# Adafruit_Gemma_M0.net
KiCad netlist of a schematic drawn in EAGLE
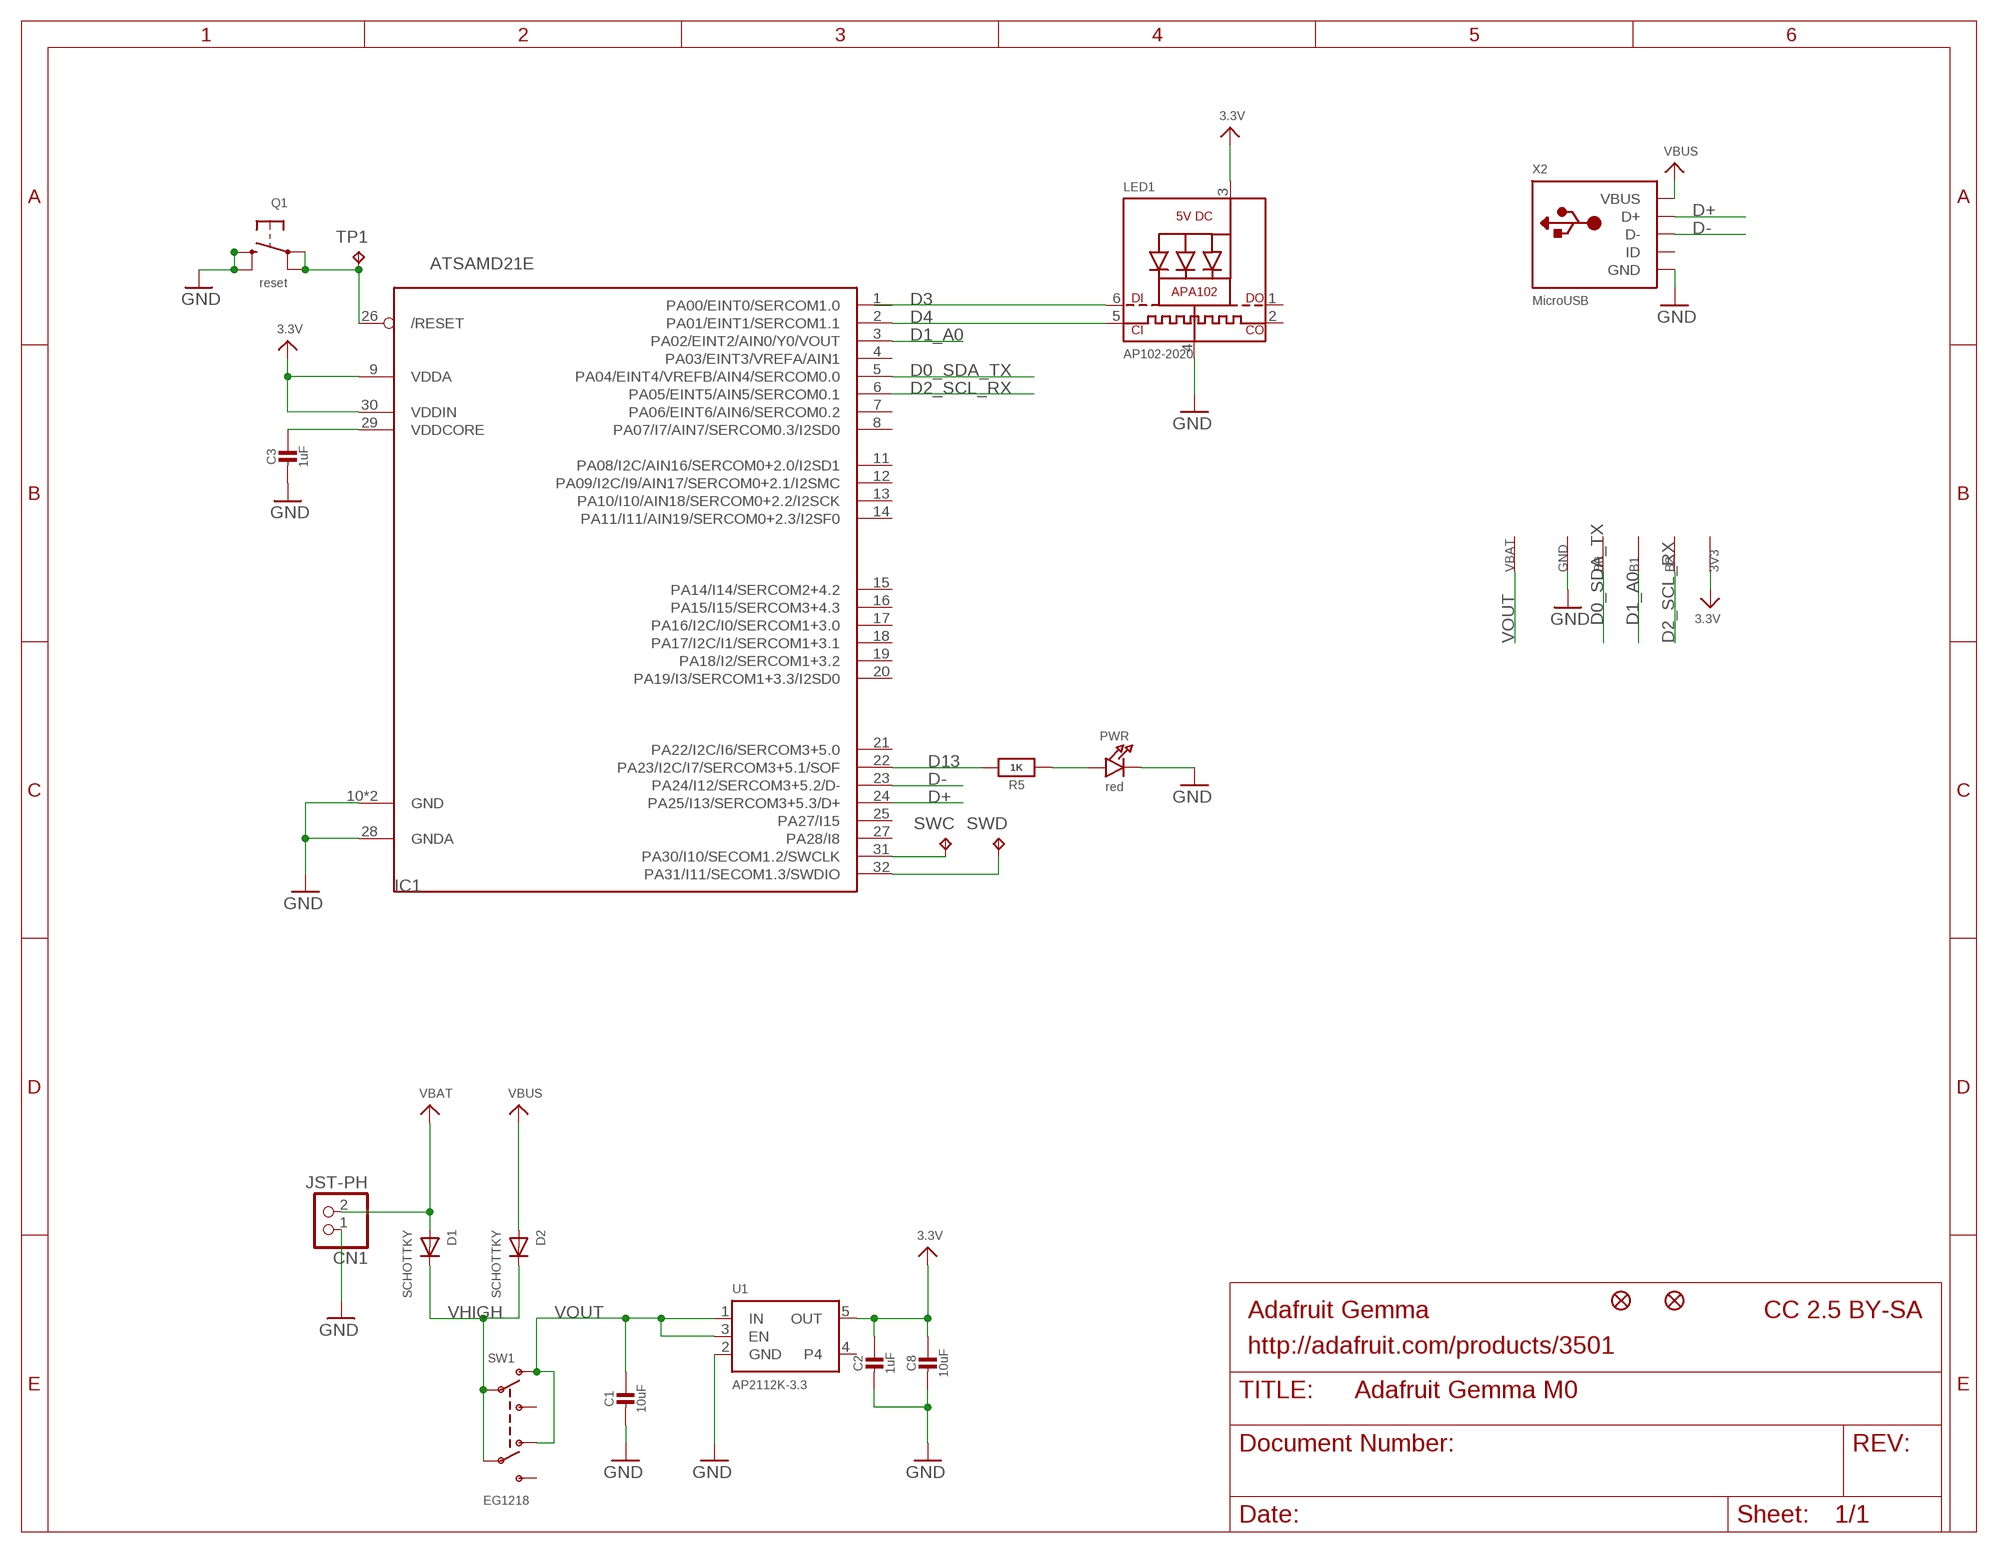
[diagram p0: schematic, sheet 1]

(export (version "E")
  (design (tool "Eeschema 10.0.6"))
  (components
    (comp (ref "3V3")
      (value "SEWTAP-ALLIGATOR")
      (footprint "eagle-import:SEWALLI")
      (libsource (lib "eagle-import") (part "SEWTAP-ALLIGATOR"))
    )
    (comp (ref "B0")
      (value "SEWTAP-ALLIGATOR")
      (footprint "eagle-import:SEWALLI")
      (libsource (lib "eagle-import") (part "SEWTAP-ALLIGATOR"))
    )
    (comp (ref "B1")
      (value "SEWTAP-ALLIGATOR")
      (footprint "eagle-import:SEWALLI")
      (libsource (lib "eagle-import") (part "SEWTAP-ALLIGATOR"))
    )
    (comp (ref "B2")
      (value "SEWTAP-ALLIGATOR")
      (footprint "eagle-import:SEWALLI")
      (libsource (lib "eagle-import") (part "SEWTAP-ALLIGATOR"))
    )
    (comp (ref "C1")
      (value "10uF")
      (footprint "eagle-import:0805-NO")
      (libsource (lib "eagle-import") (part "CAP_CERAMIC0805-NOOUTLINE"))
    )
    (comp (ref "C2")
      (value "1uF")
      (footprint "eagle-import:0603-NO")
      (libsource (lib "eagle-import") (part "CAP_CERAMIC0603_NO"))
    )
    (comp (ref "C3")
      (value "1uF")
      (footprint "eagle-import:0603-NO")
      (libsource (lib "eagle-import") (part "CAP_CERAMIC0603_NO"))
    )
    (comp (ref "C8")
      (value "10uF")
      (footprint "eagle-import:0805-NO")
      (libsource (lib "eagle-import") (part "CAP_CERAMIC0805-NOOUTLINE"))
    )
    (comp (ref "CN1")
      (value "JST-PH")
      (footprint "eagle-import:JSTPH2")
      (libsource (lib "eagle-import") (part "CON_JST_PH_2PIN"))
    )
    (comp (ref "D1")
      (value "SCHOTTKY")
      (footprint "eagle-import:SOD-123FL")
      (libsource (lib "eagle-import") (part "DIODE_SOD-123FL"))
    )
    (comp (ref "D2")
      (value "SCHOTTKY")
      (footprint "eagle-import:SOD-123FL")
      (libsource (lib "eagle-import") (part "DIODE_SOD-123FL"))
    )
    (comp (ref "GND")
      (value "SEWTAP-ALLIGATOR")
      (footprint "eagle-import:SEWALLI")
      (libsource (lib "eagle-import") (part "SEWTAP-ALLIGATOR"))
    )
    (comp (ref "IC1")
      (value "ATSAMD21E")
      (footprint "eagle-import:QFN32_5MM")
      (libsource (lib "eagle-import") (part "ATSAMD21E"))
    )
    (comp (ref "LED1")
      (value "AP102-2020")
      (footprint "eagle-import:APA102_2020")
      (libsource (lib "eagle-import") (part "APA1022020"))
    )
    (comp (ref "PWR")
      (value "red")
      (footprint "eagle-import:CHIPLED_0603_NOOUTLINE")
      (libsource (lib "eagle-import") (part "LED0603_NOOUTLINE"))
    )
    (comp (ref "Q1")
      (value "reset")
      (footprint "eagle-import:BTN_KMR2_4.6X2.8")
      (libsource (lib "eagle-import") (part "SWITCH_TACT_SMT4.6X2.8"))
    )
    (comp (ref "R5")
      (value "1K")
      (footprint "eagle-import:0603-NO")
      (libsource (lib "eagle-import") (part "RESISTOR_0603_NOOUT"))
    )
    (comp (ref "SW1")
      (value "EG1218")
      (footprint "eagle-import:EG1390")
      (libsource (lib "eagle-import") (part "SWITCH_DPDTEG1390"))
    )
    (comp (ref "SWC")
      (value "TPTP15R")
      (footprint "eagle-import:TP15R")
      (libsource (lib "eagle-import") (part "TPTP15R"))
    )
    (comp (ref "SWD")
      (value "TPTP15R")
      (footprint "eagle-import:TP15R")
      (libsource (lib "eagle-import") (part "TPTP15R"))
    )
    (comp (ref "TP1")
      (value "TPTP16R")
      (footprint "eagle-import:TP16R")
      (libsource (lib "eagle-import") (part "TPTP16R"))
    )
    (comp (ref "U$1")
      (value "FIDUCIAL_1MM")
      (footprint "eagle-import:FIDUCIAL_1MM")
      (libsource (lib "eagle-import") (part "FIDUCIAL_1MM"))
    )
    (comp (ref "U$6")
      (value "FIDUCIAL_1MM")
      (footprint "eagle-import:FIDUCIAL_1MM")
      (libsource (lib "eagle-import") (part "FIDUCIAL_1MM"))
    )
    (comp (ref "U1")
      (value "AP2112K-3.3")
      (footprint "eagle-import:SOT23-5")
      (libsource (lib "eagle-import") (part "VREG_SOT23-5"))
    )
    (comp (ref "VBAT")
      (value "SEWTAP-ALLIGATOR")
      (footprint "eagle-import:SEWALLI")
      (libsource (lib "eagle-import") (part "SEWTAP-ALLIGATOR"))
    )
    (comp (ref "X2")
      (value "MicroUSB")
      (footprint "eagle-import:4UCONN_20329_V2")
      (libsource (lib "eagle-import") (part "USB_MICRO_20329_V2"))
    )
  )
  (nets
    (net (code "1") (name "/D+") (class "Default")
      (node (ref "IC1") (pin "24") (pinfunction "PA25/I13/SERCOM3+5.3/D+_24") (pintype "bidirectional"))
      (node (ref "X2") (pin "D+") (pinfunction "D+_D+") (pintype "bidirectional"))
    )
    (net (code "2") (name "/D-") (class "Default")
      (node (ref "IC1") (pin "23") (pinfunction "PA24/I12/SERCOM3+5.2/D-_23") (pintype "bidirectional"))
      (node (ref "X2") (pin "D-") (pinfunction "D-_D-") (pintype "bidirectional"))
    )
    (net (code "3") (name "/D0_SDA_TX") (class "Default")
      (node (ref "B0") (pin "P$1") (pinfunction "SEW_P$1") (pintype "bidirectional"))
      (node (ref "IC1") (pin "5") (pinfunction "PA04/EINT4/VREFB/AIN4/SERCOM0.0_5") (pintype "bidirectional"))
    )
    (net (code "4") (name "/D1_A0") (class "Default")
      (node (ref "B1") (pin "P$1") (pinfunction "SEW_P$1") (pintype "bidirectional"))
      (node (ref "IC1") (pin "3") (pinfunction "PA02/EINT2/AIN0/Y0/VOUT_3") (pintype "bidirectional"))
    )
    (net (code "5") (name "/D2_SCL_RX") (class "Default")
      (node (ref "B2") (pin "P$1") (pinfunction "SEW_P$1") (pintype "bidirectional"))
      (node (ref "IC1") (pin "6") (pinfunction "PA05/EINT5/AIN5/SERCOM0.1_6") (pintype "bidirectional"))
    )
    (net (code "6") (name "/D3") (class "Default")
      (node (ref "IC1") (pin "1") (pinfunction "PA00/EINT0/SERCOM1.0_1") (pintype "bidirectional"))
      (node (ref "LED1") (pin "6") (pinfunction "DI_6") (pintype "input"))
    )
    (net (code "7") (name "/D4") (class "Default")
      (node (ref "IC1") (pin "2") (pinfunction "PA01/EINT1/SERCOM1.1_2") (pintype "bidirectional"))
      (node (ref "LED1") (pin "5") (pinfunction "CKI_5") (pintype "input"))
    )
    (net (code "8") (name "/D13") (class "Default")
      (node (ref "IC1") (pin "22") (pinfunction "PA23/I2C/I7/SERCOM3+5.1/SOF_22") (pintype "bidirectional"))
      (node (ref "R5") (pin "2") (pinfunction "2_2") (pintype "passive"))
    )
    (net (code "9") (name "/VHIGH") (class "Default")
      (node (ref "D1") (pin "C") (pinfunction "C_C") (pintype "passive"))
      (node (ref "D2") (pin "C") (pinfunction "C_C") (pintype "passive"))
      (node (ref "SW1") (pin "P1") (pinfunction "P1_P1") (pintype "passive"))
      (node (ref "SW1") (pin "P2") (pinfunction "P2_P2") (pintype "passive"))
    )
    (net (code "10") (name "/VOUT") (class "Default")
      (node (ref "C1") (pin "1") (pinfunction "1_1") (pintype "passive"))
      (node (ref "SW1") (pin "O1") (pinfunction "O1_O1") (pintype "passive"))
      (node (ref "SW1") (pin "O2") (pinfunction "O2_O2") (pintype "passive"))
      (node (ref "U1") (pin "1") (pinfunction "IN_1") (pintype "power_in"))
      (node (ref "U1") (pin "3") (pinfunction "EN_3") (pintype "input"))
      (node (ref "VBAT") (pin "P$1") (pinfunction "SEW_P$1") (pintype "bidirectional"))
    )
    (net (code "11") (name "3.3V") (class "Default")
      (node (ref "3V3") (pin "P$1") (pinfunction "SEW_P$1") (pintype "bidirectional"))
      (node (ref "C2") (pin "1") (pinfunction "1_1") (pintype "passive"))
      (node (ref "C8") (pin "1") (pinfunction "1_1") (pintype "passive"))
      (node (ref "IC1") (pin "30") (pinfunction "VDDIN_30") (pintype "power_in"))
      (node (ref "IC1") (pin "9") (pinfunction "VDDA_9") (pintype "power_in"))
      (node (ref "LED1") (pin "3") (pinfunction "VDD_3") (pintype "power_in"))
      (node (ref "U1") (pin "5") (pinfunction "OUT_5") (pintype "power_in"))
    )
    (net (code "12") (name "GND") (class "Default")
      (node (ref "C1") (pin "2") (pinfunction "2_2") (pintype "passive"))
      (node (ref "C2") (pin "2") (pinfunction "2_2") (pintype "passive"))
      (node (ref "C3") (pin "2") (pinfunction "2_2") (pintype "passive"))
      (node (ref "C8") (pin "2") (pinfunction "2_2") (pintype "passive"))
      (node (ref "CN1") (pin "1") (pinfunction "1_1") (pintype "passive"))
      (node (ref "GND") (pin "P$1") (pinfunction "SEW_P$1") (pintype "bidirectional"))
      (node (ref "IC1") (pin "10") (pinfunction "GND_10") (pintype "power_in"))
      (node (ref "IC1") (pin "28") (pinfunction "GNDA_28") (pintype "power_in"))
      (node (ref "IC1") (pin "33") (pinfunction "GND_33") (pintype "power_in"))
      (node (ref "LED1") (pin "4") (pinfunction "GND_4") (pintype "power_in"))
      (node (ref "PWR") (pin "C") (pinfunction "C_C") (pintype "passive"))
      (node (ref "Q1") (pin "B") (pinfunction "S_B") (pintype "passive"))
      (node (ref "Q1") (pin "B'") (pinfunction "S1_B'") (pintype "passive"))
      (node (ref "U1") (pin "2") (pinfunction "GND_2") (pintype "power_in"))
      (node (ref "X2") (pin "BASE@1") (pinfunction "GND_BASE@1") (pintype "power_in"))
      (node (ref "X2") (pin "BASE@2") (pinfunction "GND_BASE@2") (pintype "power_in"))
      (node (ref "X2") (pin "GND") (pinfunction "GND_GND") (pintype "power_in"))
      (node (ref "X2") (pin "SPRT@1") (pinfunction "GND_SPRT@1") (pintype "power_in"))
      (node (ref "X2") (pin "SPRT@2") (pinfunction "GND_SPRT@2") (pintype "power_in"))
      (node (ref "X2") (pin "SPRT@3") (pinfunction "GND_SPRT@3") (pintype "power_in"))
      (node (ref "X2") (pin "SPRT@4") (pinfunction "GND_SPRT@4") (pintype "power_in"))
    )
    (net (code "13") (name "Net-(IC1-PA30{slash}I10{slash}SECOM1.2{slash}SWCLK)") (class "Default")
      (node (ref "IC1") (pin "31") (pinfunction "PA30/I10/SECOM1.2/SWCLK_31") (pintype "bidirectional"))
      (node (ref "SWC") (pin "TP") (pinfunction "TP_TP") (pintype "input"))
    )
    (net (code "14") (name "Net-(IC1-PA31{slash}I11{slash}SECOM1.3{slash}SWDIO)") (class "Default")
      (node (ref "IC1") (pin "32") (pinfunction "PA31/I11/SECOM1.3/SWDIO_32") (pintype "bidirectional"))
      (node (ref "SWD") (pin "TP") (pinfunction "TP_TP") (pintype "input"))
    )
    (net (code "15") (name "Net-(IC1-VDDCORE)") (class "Default")
      (node (ref "C3") (pin "1") (pinfunction "1_1") (pintype "passive"))
      (node (ref "IC1") (pin "29") (pinfunction "VDDCORE_29") (pintype "power_in"))
    )
    (net (code "16") (name "Net-(IC1-{slash}RESET)") (class "Default")
      (node (ref "IC1") (pin "26") (pinfunction "/RESET_26") (pintype "bidirectional"))
      (node (ref "Q1") (pin "A") (pinfunction "P_A") (pintype "passive"))
      (node (ref "Q1") (pin "A'") (pinfunction "P1_A'") (pintype "passive"))
      (node (ref "TP1") (pin "TP") (pinfunction "TP_TP") (pintype "input"))
    )
    (net (code "17") (name "Net-(PWR-PadA)") (class "Default")
      (node (ref "PWR") (pin "A") (pinfunction "A_A") (pintype "passive"))
      (node (ref "R5") (pin "1") (pinfunction "1_1") (pintype "passive"))
    )
    (net (code "18") (name "VBAT") (class "Default")
      (node (ref "CN1") (pin "2") (pinfunction "2_2") (pintype "passive"))
      (node (ref "D1") (pin "A") (pinfunction "A_A") (pintype "passive"))
    )
    (net (code "19") (name "VBUS") (class "Default")
      (node (ref "D2") (pin "A") (pinfunction "A_A") (pintype "passive"))
      (node (ref "X2") (pin "VBUS") (pinfunction "VBUS_VBUS") (pintype "power_in"))
    )
    (net (code "20") (name "unconnected-(IC1-PA03{slash}EINT3{slash}VREFA{slash}AIN1-Pad4)") (class "Default")
      (node (ref "IC1") (pin "4") (pinfunction "PA03/EINT3/VREFA/AIN1_4") (pintype "bidirectional"))
    )
    (net (code "21") (name "unconnected-(IC1-PA06{slash}EINT6{slash}AIN6{slash}SERCOM0.2-Pad7)") (class "Default")
      (node (ref "IC1") (pin "7") (pinfunction "PA06/EINT6/AIN6/SERCOM0.2_7") (pintype "bidirectional"))
    )
    (net (code "22") (name "unconnected-(IC1-PA07{slash}I7{slash}AIN7{slash}SERCOM0.3{slash}I2SD0-Pad8)") (class "Default")
      (node (ref "IC1") (pin "8") (pinfunction "PA07/I7/AIN7/SERCOM0.3/I2SD0_8") (pintype "bidirectional"))
    )
    (net (code "23") (name "unconnected-(IC1-PA08{slash}I2C{slash}AIN16{slash}SERCOM0+2.0{slash}I2SD1-Pad11)") (class "Default")
      (node (ref "IC1") (pin "11") (pinfunction "PA08/I2C/AIN16/SERCOM0+2.0/I2SD1_11") (pintype "bidirectional"))
    )
    (net (code "24") (name "unconnected-(IC1-PA09{slash}I2C{slash}I9{slash}AIN17{slash}SERCOM0+2.1{slash}I2SMC-Pad12)") (class "Default")
      (node (ref "IC1") (pin "12") (pinfunction "PA09/I2C/I9/AIN17/SERCOM0+2.1/I2SMC_12") (pintype "bidirectional"))
    )
    (net (code "25") (name "unconnected-(IC1-PA10{slash}I10{slash}AIN18{slash}SERCOM0+2.2{slash}I2SCK-Pad13)") (class "Default")
      (node (ref "IC1") (pin "13") (pinfunction "PA10/I10/AIN18/SERCOM0+2.2/I2SCK_13") (pintype "bidirectional"))
    )
    (net (code "26") (name "unconnected-(IC1-PA11{slash}I11{slash}AIN19{slash}SERCOM0+2.3{slash}I2SF0-Pad14)") (class "Default")
      (node (ref "IC1") (pin "14") (pinfunction "PA11/I11/AIN19/SERCOM0+2.3/I2SF0_14") (pintype "bidirectional"))
    )
    (net (code "27") (name "unconnected-(IC1-PA14{slash}I14{slash}SERCOM2+4.2-Pad15)") (class "Default")
      (node (ref "IC1") (pin "15") (pinfunction "PA14/I14/SERCOM2+4.2_15") (pintype "bidirectional"))
    )
    (net (code "28") (name "unconnected-(IC1-PA15{slash}I15{slash}SERCOM3+4.3-Pad16)") (class "Default")
      (node (ref "IC1") (pin "16") (pinfunction "PA15/I15/SERCOM3+4.3_16") (pintype "bidirectional"))
    )
    (net (code "29") (name "unconnected-(IC1-PA16{slash}I2C{slash}I0{slash}SERCOM1+3.0-Pad17)") (class "Default")
      (node (ref "IC1") (pin "17") (pinfunction "PA16/I2C/I0/SERCOM1+3.0_17") (pintype "bidirectional"))
    )
    (net (code "30") (name "unconnected-(IC1-PA17{slash}I2C{slash}I1{slash}SERCOM1+3.1-Pad18)") (class "Default")
      (node (ref "IC1") (pin "18") (pinfunction "PA17/I2C/I1/SERCOM1+3.1_18") (pintype "bidirectional"))
    )
    (net (code "31") (name "unconnected-(IC1-PA18{slash}I2{slash}SERCOM1+3.2-Pad19)") (class "Default")
      (node (ref "IC1") (pin "19") (pinfunction "PA18/I2/SERCOM1+3.2_19") (pintype "bidirectional"))
    )
    (net (code "32") (name "unconnected-(IC1-PA19{slash}I3{slash}SERCOM1+3.3{slash}I2SD0-Pad20)") (class "Default")
      (node (ref "IC1") (pin "20") (pinfunction "PA19/I3/SERCOM1+3.3/I2SD0_20") (pintype "bidirectional"))
    )
    (net (code "33") (name "unconnected-(IC1-PA22{slash}I2C{slash}I6{slash}SERCOM3+5.0-Pad21)") (class "Default")
      (node (ref "IC1") (pin "21") (pinfunction "PA22/I2C/I6/SERCOM3+5.0_21") (pintype "bidirectional"))
    )
    (net (code "34") (name "unconnected-(IC1-PA27{slash}I15-Pad25)") (class "Default")
      (node (ref "IC1") (pin "25") (pinfunction "PA27/I15_25") (pintype "bidirectional"))
    )
    (net (code "35") (name "unconnected-(IC1-PA28{slash}I8-Pad27)") (class "Default")
      (node (ref "IC1") (pin "27") (pinfunction "PA28/I8_27") (pintype "bidirectional"))
    )
    (net (code "36") (name "unconnected-(LED1-CKO-Pad2)") (class "Default")
      (node (ref "LED1") (pin "2") (pinfunction "CKO_2") (pintype "output"))
    )
    (net (code "37") (name "unconnected-(LED1-DO-Pad1)") (class "Default")
      (node (ref "LED1") (pin "1") (pinfunction "DO_1") (pintype "output"))
    )
    (net (code "38") (name "unconnected-(SW1-PadS1)") (class "Default")
      (node (ref "SW1") (pin "S1") (pinfunction "S1_S1") (pintype "passive"))
    )
    (net (code "39") (name "unconnected-(SW1-PadS2)") (class "Default")
      (node (ref "SW1") (pin "S2") (pinfunction "S2_S2") (pintype "passive"))
    )
    (net (code "40") (name "unconnected-(U1-P4-Pad4)") (class "Default")
      (node (ref "U1") (pin "4") (pinfunction "P4_4") (pintype "bidirectional"))
    )
    (net (code "41") (name "unconnected-(X2-PadID)") (class "Default")
      (node (ref "X2") (pin "ID") (pinfunction "ID_ID") (pintype "bidirectional"))
    )
  )
)
